# usb_ttl_schematic.net
KiCad netlist of a schematic drawn in Altium Designer
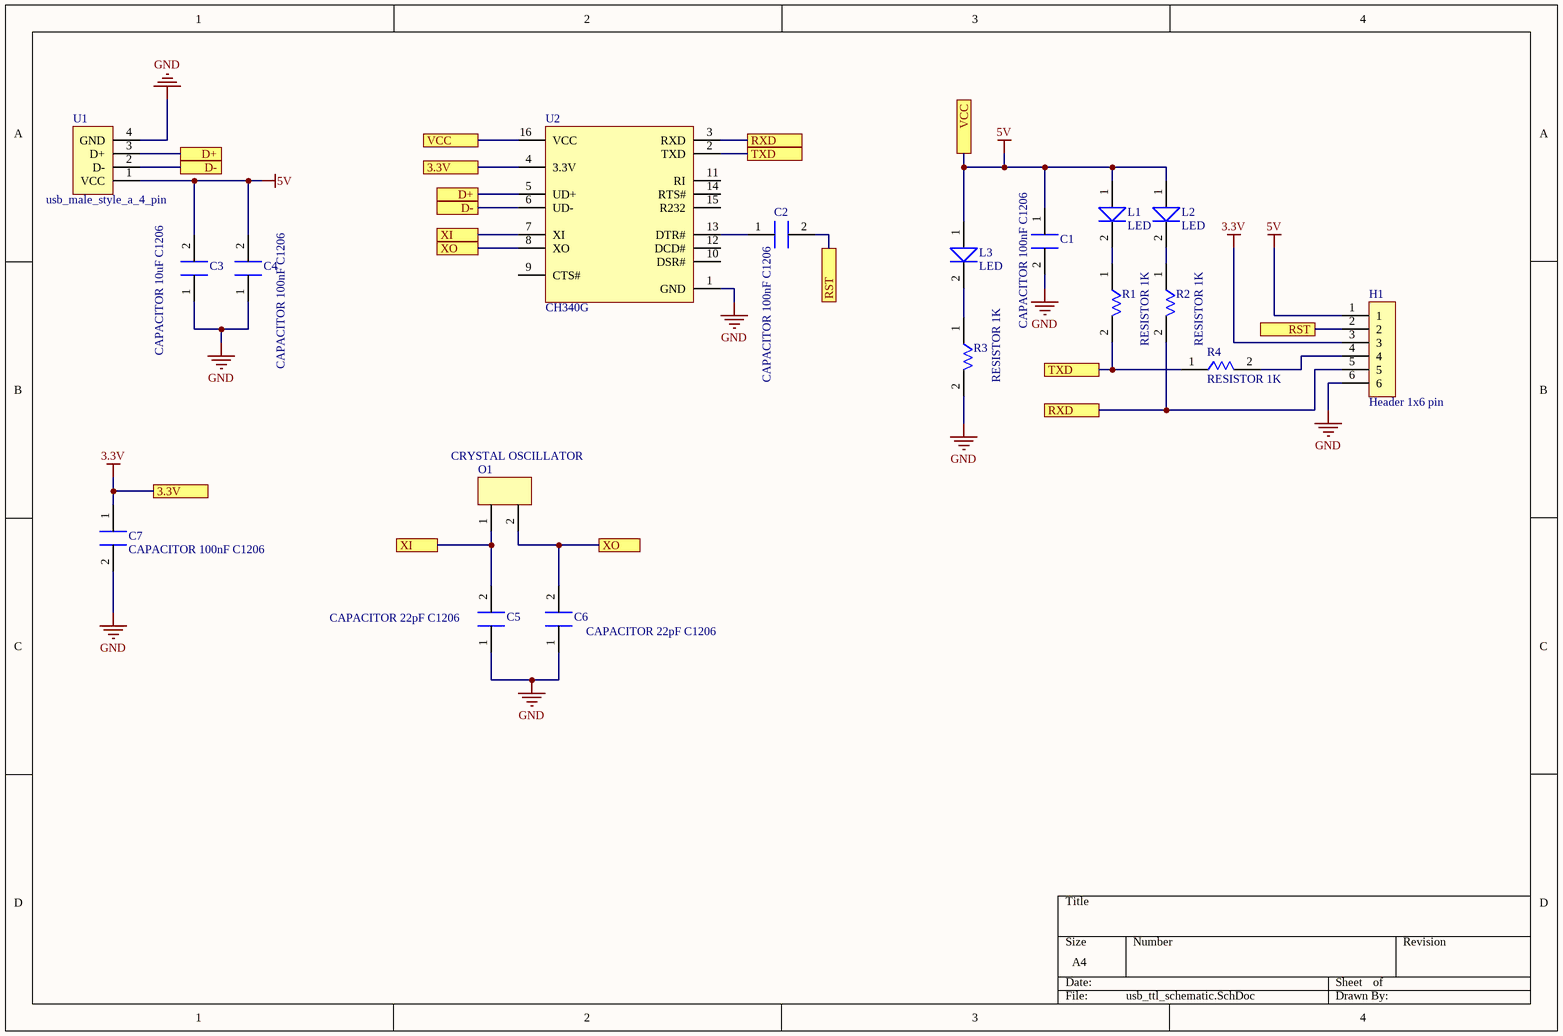
[diagram p0: usb_ttl_schematic.SchDoc]

(export (version "E")
  (design (tool "Eeschema 10.0.6"))
  (components
    (comp (ref "C1")
      (value "CAPACITOR 100nF C1206")
      (footprint "CAPACITOR C1206")
      (description "CAP 100nF C1206")
      (libsource (lib "usb_ttl_schematic_library") (part "CAPACITOR 100nF C1206"))
    )
    (comp (ref "C2")
      (value "CAPACITOR 100nF C1206")
      (footprint "CAPACITOR C1206")
      (description "CAP 100nF C1206")
      (libsource (lib "usb_ttl_schematic_library") (part "CAPACITOR 100nF C1206"))
    )
    (comp (ref "C3")
      (value "CAPACITOR 10uF C1206")
      (footprint "CAPACITOR C1206")
      (description "CAP 10 uF C1206")
      (libsource (lib "usb_ttl_schematic_library") (part "CAPACITOR 10uF C1206"))
    )
    (comp (ref "C4")
      (value "CAPACITOR 100nF C1206")
      (footprint "CAPACITOR C1206")
      (description "CAP 100nF C1206")
      (libsource (lib "usb_ttl_schematic_library") (part "CAPACITOR 100nF C1206"))
    )
    (comp (ref "C5")
      (value "CAPACITOR 22pF C1206")
      (footprint "CAPACITOR C1206")
      (description "CAP 22pF C1206")
      (libsource (lib "usb_ttl_schematic_library") (part "CAPACITOR 22pF C1206"))
    )
    (comp (ref "C6")
      (value "CAPACITOR 22pF C1206")
      (footprint "CAPACITOR C1206")
      (description "CAP 22pF C1206")
      (libsource (lib "usb_ttl_schematic_library") (part "CAPACITOR 22pF C1206"))
    )
    (comp (ref "C7")
      (value "CAPACITOR 100nF C1206")
      (footprint "CAPACITOR C1206")
      (description "CAP 100nF C1206")
      (libsource (lib "usb_ttl_schematic_library") (part "CAPACITOR 100nF C1206"))
    )
    (comp (ref "H1")
      (value "Header 1x6 pin")
      (footprint "header 1x6")
      (description "header 1x6 pim ,2.54 pin gap")
      (libsource (lib "usb_ttl_schematic_library") (part "Header 1x6 pin"))
    )
    (comp (ref "L1")
      (value "LED")
      (footprint "led")
      (libsource (lib "usb_ttl_schematic_library") (part "LED"))
    )
    (comp (ref "L2")
      (value "LED")
      (footprint "led")
      (libsource (lib "usb_ttl_schematic_library") (part "LED"))
    )
    (comp (ref "L3")
      (value "LED")
      (footprint "led")
      (libsource (lib "usb_ttl_schematic_library") (part "LED"))
    )
    (comp (ref "O1")
      (value "CRYSTAL OSCILLATOR")
      (footprint "CRYSTAL OSC.")
      (description "HC49 ,CRYSTAL OSCILLATOR 12MHz")
      (libsource (lib "usb_ttl_schematic_library") (part "CRYSTAL OSCILLATOR"))
    )
    (comp (ref "R1")
      (value "RESISTOR 1K")
      (footprint "RESISTOR 1K")
      (libsource (lib "usb_ttl_schematic_library") (part "RESISTOR 1K"))
    )
    (comp (ref "R2")
      (value "RESISTOR 1K")
      (footprint "RESISTOR 1K")
      (libsource (lib "usb_ttl_schematic_library") (part "RESISTOR 1K"))
    )
    (comp (ref "R3")
      (value "RESISTOR 1K")
      (footprint "RESISTOR 1K")
      (libsource (lib "usb_ttl_schematic_library") (part "RESISTOR 1K"))
    )
    (comp (ref "R4")
      (value "RESISTOR 1K")
      (footprint "RESISTOR 1K")
      (libsource (lib "usb_ttl_schematic_library") (part "RESISTOR 1K"))
    )
    (comp (ref "U1")
      (value "usb_male_style_a_4_pin")
      (footprint "usb_style a_male 4_contact")
      (description "USB 4 PIN ,STYLE A,MALE")
      (libsource (lib "usb_ttl_schematic_library") (part "usb_male_style_a_4_pin"))
    )
    (comp (ref "U2")
      (value "CH340G")
      (footprint "CH340G")
      (description "CH320G ,USB_TO_TTL CONVERTER")
      (libsource (lib "usb_ttl_schematic_library") (part "CH340G"))
    )
  )
  (nets
    (net (code "1") (name "/D+") (class "Default")
      (node (ref "U1") (pin "3") (pinfunction "D+_3") (pintype "passive"))
      (node (ref "U2") (pin "5") (pinfunction "UD+_5") (pintype "passive"))
    )
    (net (code "2") (name "/D-") (class "Default")
      (node (ref "U1") (pin "2") (pinfunction "D-_2") (pintype "passive"))
      (node (ref "U2") (pin "6") (pinfunction "UD-_6") (pintype "passive"))
    )
    (net (code "3") (name "/RST") (class "Default")
      (node (ref "C2") (pin "2") (pinfunction "2_2") (pintype "passive"))
      (node (ref "H1") (pin "2") (pinfunction "2_2") (pintype "passive"))
    )
    (net (code "4") (name "/RXD") (class "Default")
      (node (ref "H1") (pin "5") (pinfunction "5_5") (pintype "passive"))
      (node (ref "R2") (pin "2") (pintype "passive"))
      (node (ref "U2") (pin "3") (pinfunction "RXD_3") (pintype "passive"))
    )
    (net (code "5") (name "/TXD") (class "Default")
      (node (ref "R1") (pin "2") (pintype "passive"))
      (node (ref "R4") (pin "1") (pintype "passive"))
      (node (ref "U2") (pin "2") (pinfunction "TXD_2") (pintype "passive"))
    )
    (net (code "6") (name "/XI") (class "Default")
      (node (ref "C5") (pin "2") (pinfunction "2_2") (pintype "passive"))
      (node (ref "O1") (pin "1") (pintype "passive"))
      (node (ref "U2") (pin "7") (pinfunction "XI_7") (pintype "passive"))
    )
    (net (code "7") (name "/XO") (class "Default")
      (node (ref "C6") (pin "2") (pinfunction "2_2") (pintype "passive"))
      (node (ref "O1") (pin "2") (pintype "passive"))
      (node (ref "U2") (pin "8") (pinfunction "XO_8") (pintype "passive"))
    )
    (net (code "8") (name "3.3V") (class "Default")
      (node (ref "C7") (pin "1") (pinfunction "1_1") (pintype "passive"))
      (node (ref "H1") (pin "3") (pinfunction "3_3") (pintype "passive"))
      (node (ref "U2") (pin "4") (pinfunction "3.3V_4") (pintype "passive"))
    )
    (net (code "9") (name "5V") (class "Default")
      (node (ref "C1") (pin "1") (pinfunction "1_1") (pintype "passive"))
      (node (ref "C3") (pin "2") (pinfunction "2_2") (pintype "passive"))
      (node (ref "C4") (pin "2") (pinfunction "2_2") (pintype "passive"))
      (node (ref "H1") (pin "1") (pinfunction "1_1") (pintype "passive"))
      (node (ref "L1") (pin "1") (pintype "passive"))
      (node (ref "L2") (pin "1") (pintype "passive"))
      (node (ref "L3") (pin "1") (pintype "passive"))
      (node (ref "U1") (pin "1") (pinfunction "VCC_1") (pintype "passive"))
      (node (ref "U2") (pin "16") (pinfunction "VCC_16") (pintype "passive"))
    )
    (net (code "10") (name "GND") (class "Default")
      (node (ref "C1") (pin "2") (pinfunction "2_2") (pintype "passive"))
      (node (ref "C3") (pin "1") (pinfunction "1_1") (pintype "passive"))
      (node (ref "C4") (pin "1") (pinfunction "1_1") (pintype "passive"))
      (node (ref "C5") (pin "1") (pinfunction "1_1") (pintype "passive"))
      (node (ref "C6") (pin "1") (pinfunction "1_1") (pintype "passive"))
      (node (ref "C7") (pin "2") (pinfunction "2_2") (pintype "passive"))
      (node (ref "H1") (pin "6") (pinfunction "6_6") (pintype "passive"))
      (node (ref "R3") (pin "2") (pintype "passive"))
      (node (ref "U1") (pin "4") (pinfunction "GND_4") (pintype "passive"))
      (node (ref "U2") (pin "1") (pinfunction "GND_1") (pintype "passive"))
    )
    (net (code "11") (name "Net-(H1-Pad4)") (class "Default")
      (node (ref "H1") (pin "4") (pinfunction "4_4") (pintype "passive"))
      (node (ref "R4") (pin "2") (pintype "passive"))
    )
    (net (code "12") (name "Net-(L1-Pad2)") (class "Default")
      (node (ref "L1") (pin "2") (pintype "passive"))
      (node (ref "R1") (pin "1") (pintype "passive"))
    )
    (net (code "13") (name "Net-(L2-Pad2)") (class "Default")
      (node (ref "L2") (pin "2") (pintype "passive"))
      (node (ref "R2") (pin "1") (pintype "passive"))
    )
    (net (code "14") (name "Net-(L3-Pad2)") (class "Default")
      (node (ref "L3") (pin "2") (pintype "passive"))
      (node (ref "R3") (pin "1") (pintype "passive"))
    )
    (net (code "15") (name "Net-(U2-DTR#)") (class "Default")
      (node (ref "C2") (pin "1") (pinfunction "1_1") (pintype "passive"))
      (node (ref "U2") (pin "13") (pinfunction "DTR#_13") (pintype "passive"))
    )
    (net (code "16") (name "unconnected-(U2-CTS#-Pad9)") (class "Default")
      (node (ref "U2") (pin "9") (pinfunction "CTS#_9") (pintype "passive"))
    )
    (net (code "17") (name "unconnected-(U2-DCD#-Pad12)") (class "Default")
      (node (ref "U2") (pin "12") (pinfunction "DCD#_12") (pintype "passive"))
    )
    (net (code "18") (name "unconnected-(U2-DSR#-Pad10)") (class "Default")
      (node (ref "U2") (pin "10") (pinfunction "DSR#_10") (pintype "passive"))
    )
    (net (code "19") (name "unconnected-(U2-R232-Pad15)") (class "Default")
      (node (ref "U2") (pin "15") (pinfunction "R232_15") (pintype "passive"))
    )
    (net (code "20") (name "unconnected-(U2-RI-Pad11)") (class "Default")
      (node (ref "U2") (pin "11") (pinfunction "RI_11") (pintype "passive"))
    )
    (net (code "21") (name "unconnected-(U2-RTS#-Pad14)") (class "Default")
      (node (ref "U2") (pin "14") (pinfunction "RTS#_14") (pintype "passive"))
    )
  )
)
